# CAN_Sheet.net
KiCad netlist of a schematic drawn in Altium Designer
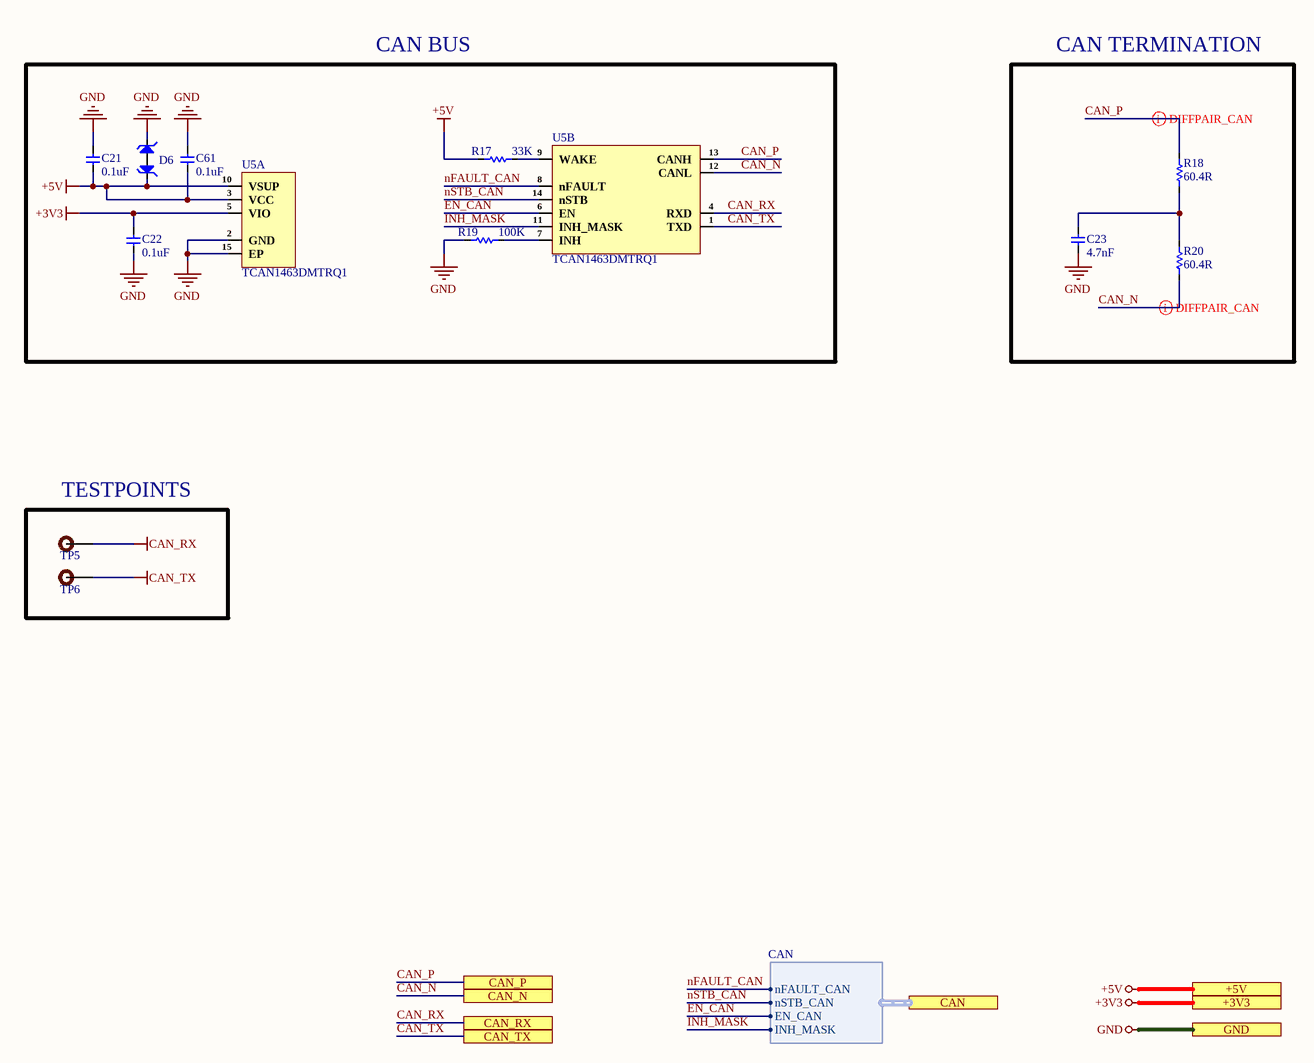
[diagram p0: CAN_Sheet.SchDoc]

(export (version "E")
  (design (tool "Eeschema 10.0.6"))
  (components
    (comp (ref "C21")
      (value "0.1uF")
      (footprint "Cap-0402")
      (description "CAP CER 0.1UF 16V X7R 0402")
      (fields
        (field (name "MANUFACTURER") "Yageo")
        (field (name "MANUFACTURER PART NUMBER") "CC0402JRX7R7BB104")
      )
      (libsource (lib "eSpark Libraries") (part "CC0402JRX7R7BB104"))
    )
    (comp (ref "C22")
      (value "0.1uF")
      (footprint "Cap-0402")
      (description "CAP CER 0.1UF 16V X7R 0402")
      (fields
        (field (name "MANUFACTURER") "Yageo")
        (field (name "MANUFACTURER PART NUMBER") "CC0402JRX7R7BB104")
      )
      (libsource (lib "eSpark Libraries") (part "CC0402JRX7R7BB104"))
    )
    (comp (ref "C23")
      (value "4.7nF")
      (footprint "Cap-0402")
      (description "CAP CER 4700PF 50V X7R 0402")
      (fields
        (field (name "MANUFACTURER") "Yageo")
        (field (name "MANUFACTURER PART NUMBER") "CC0402KRX7R9BB472")
      )
      (libsource (lib "eSpark Libraries") (part "CC0402KRX7R9BB472"))
    )
    (comp (ref "C61")
      (value "0.1uF")
      (footprint "Cap-0402")
      (description "CAP CER 0.1UF 16V X7R 0402")
      (fields
        (field (name "MANUFACTURER") "Yageo")
        (field (name "MANUFACTURER PART NUMBER") "CC0402JRX7R7BB104")
      )
      (libsource (lib "eSpark Libraries") (part "CC0402JRX7R7BB104"))
    )
    (comp (ref "D6")
      (value "PESD5V0H1BSFYL")
      (footprint "DSN0603-2")
      (description "TVS DIODE 5VWM 6.3VC DSN0603-2")
      (fields (field (name "MANUFACTURER") "Nexperia") (field (name "LCSC PART NUMBER") "C477989"))
      (libsource (lib "eSpark Libraries") (part "PESD5V0H1BSFYL"))
    )
    (comp (ref "R17")
      (value "33K")
      (footprint "Res-0402")
      (description "RES 33K OHM 1% 1/16W 0402")
      (fields
        (field (name "MANUFACTURER") "YAGEO")
        (field (name "MANUFACTURER PART NUMBER") "RC0402FR-0733KL")
      )
      (libsource (lib "eSpark Libraries") (part "RC0402FR-0733KL"))
    )
    (comp (ref "R18")
      (value "60.4R")
      (footprint "Res-0603")
      (description "100mW Thick Film Resistors ±100ppm/℃ ±1% 60.4Ω 0603 Chip Resistor - Surface Mount ROHS")
      (fields
        (field (name "MANUFACTURER PART NUMBER") "RTT0360R4FTP")
        (field (name "LCSC PART NUMBER") "C103744")
      )
      (libsource (lib "eSpark Libraries") (part "RTT0360R4FTP"))
    )
    (comp (ref "R19")
      (value "100K")
      (footprint "Res-0402")
      (description "RES 100K OHM 1% 1/16W 0402")
      (fields
        (field (name "MANUFACTURER") "Yageo")
        (field (name "MANUFACTURER PART NUMBER") "RC0402FR-07100KL")
      )
      (libsource (lib "eSpark Libraries") (part "RC0402FR-07100KL"))
    )
    (comp (ref "R20")
      (value "60.4R")
      (footprint "Res-0603")
      (description "100mW Thick Film Resistors ±100ppm/℃ ±1% 60.4Ω 0603 Chip Resistor - Surface Mount ROHS")
      (fields
        (field (name "MANUFACTURER PART NUMBER") "RTT0360R4FTP")
        (field (name "LCSC PART NUMBER") "C103744")
      )
      (libsource (lib "eSpark Libraries") (part "RTT0360R4FTP"))
    )
    (comp (ref "TP5")
      (value "TEST POINT")
      (footprint "Test-point")
      (description "Test Point ON")
      (libsource (lib "eSpark Libraries") (part "TEST POINT"))
    )
    (comp (ref "TP6")
      (value "TEST POINT")
      (footprint "Test-point")
      (description "Test Point ON")
      (libsource (lib "eSpark Libraries") (part "TEST POINT"))
    )
    (comp (ref "U5")
      (value "TCAN1463DMTRQ1")
      (footprint "VSON-14(3x4.5)")
      (description "IC TRANSCEIVER HALF 1/1 14VSON")
      (fields (field (name "MANUFACTURER") "Texas Instruments") (field (name "LCSC PART NUMBER") "C5215823"))
      (libsource (lib "eSpark Libraries") (part "TCAN1463DMTRQ1"))
    )
  )
  (nets
    (net (code "2") (name "+3V3") (class "Default")
      (node (ref "C22") (pin "2") (pinfunction "2_2") (pintype "passive"))
      (node (ref "U5") (pin "5") (pinfunction "VIO_5") (pintype "passive"))
    )
    (net (code "3") (name "+5V") (class "Default")
      (node (ref "C21") (pin "1") (pinfunction "1_1") (pintype "passive"))
      (node (ref "C61") (pin "1") (pinfunction "1_1") (pintype "passive"))
      (node (ref "D6") (pin "1") (pinfunction "1_1") (pintype "passive"))
      (node (ref "R17") (pin "1") (pinfunction "1_1") (pintype "passive"))
      (node (ref "U5") (pin "10") (pinfunction "VSUP_10") (pintype "passive"))
      (node (ref "U5") (pin "3") (pinfunction "VCC_3") (pintype "passive"))
    )
    (net (code "4") (name "/CAN_N") (class "Default")
      (node (ref "R20") (pin "2") (pinfunction "2_2") (pintype "passive"))
      (node (ref "U5") (pin "12") (pinfunction "CANL_12") (pintype "passive"))
    )
    (net (code "5") (name "/CAN_P") (class "Default")
      (node (ref "R18") (pin "1") (pinfunction "1_1") (pintype "passive"))
      (node (ref "U5") (pin "13") (pinfunction "CANH_13") (pintype "passive"))
    )
    (net (code "6") (name "/EN_CAN") (class "Default")
      (node (ref "U5") (pin "6") (pinfunction "EN_6") (pintype "passive"))
    )
    (net (code "7") (name "/INH_MASK") (class "Default")
      (node (ref "U5") (pin "11") (pinfunction "INH_MASK_11") (pintype "passive"))
    )
    (net (code "8") (name "/nFAULT_CAN") (class "Default")
      (node (ref "U5") (pin "8") (pinfunction "nFAULT_8") (pintype "passive"))
    )
    (net (code "9") (name "/nSTB_CAN") (class "Default")
      (node (ref "U5") (pin "14") (pinfunction "nSTB_14") (pintype "passive"))
    )
    (net (code "11") (name "CAN_RX") (class "Default")
      (node (ref "TP5") (pin "1") (pinfunction "1_1") (pintype "passive"))
      (node (ref "U5") (pin "4") (pinfunction "RXD_4") (pintype "passive"))
    )
    (net (code "12") (name "CAN_TX") (class "Default")
      (node (ref "TP6") (pin "1") (pinfunction "1_1") (pintype "passive"))
      (node (ref "U5") (pin "1") (pinfunction "TXD_1") (pintype "passive"))
    )
    (net (code "13") (name "GND") (class "Default")
      (node (ref "C21") (pin "2") (pinfunction "2_2") (pintype "passive"))
      (node (ref "C22") (pin "1") (pinfunction "1_1") (pintype "passive"))
      (node (ref "C23") (pin "2") (pinfunction "2_2") (pintype "passive"))
      (node (ref "C61") (pin "2") (pinfunction "2_2") (pintype "passive"))
      (node (ref "D6") (pin "2") (pinfunction "2_2") (pintype "passive"))
      (node (ref "R19") (pin "1") (pinfunction "1_1") (pintype "passive"))
      (node (ref "U5") (pin "15") (pinfunction "EP_15") (pintype "passive"))
      (node (ref "U5") (pin "2") (pinfunction "GND_2") (pintype "passive"))
    )
    (net (code "14") (name "Net-(C23-Pad1)") (class "Default")
      (node (ref "C23") (pin "1") (pinfunction "1_1") (pintype "passive"))
      (node (ref "R18") (pin "2") (pinfunction "2_2") (pintype "passive"))
      (node (ref "R20") (pin "1") (pinfunction "1_1") (pintype "passive"))
    )
    (net (code "15") (name "Net-(U5B-INH)") (class "Default")
      (node (ref "R19") (pin "2") (pinfunction "2_2") (pintype "passive"))
      (node (ref "U5") (pin "7") (pinfunction "INH_7") (pintype "passive"))
    )
    (net (code "16") (name "Net-(U5B-WAKE)") (class "Default")
      (node (ref "R17") (pin "2") (pinfunction "2_2") (pintype "passive"))
      (node (ref "U5") (pin "9") (pinfunction "WAKE_9") (pintype "passive"))
    )
  )
)
